# Inputs.net
KiCad netlist of a schematic drawn in Altium Designer
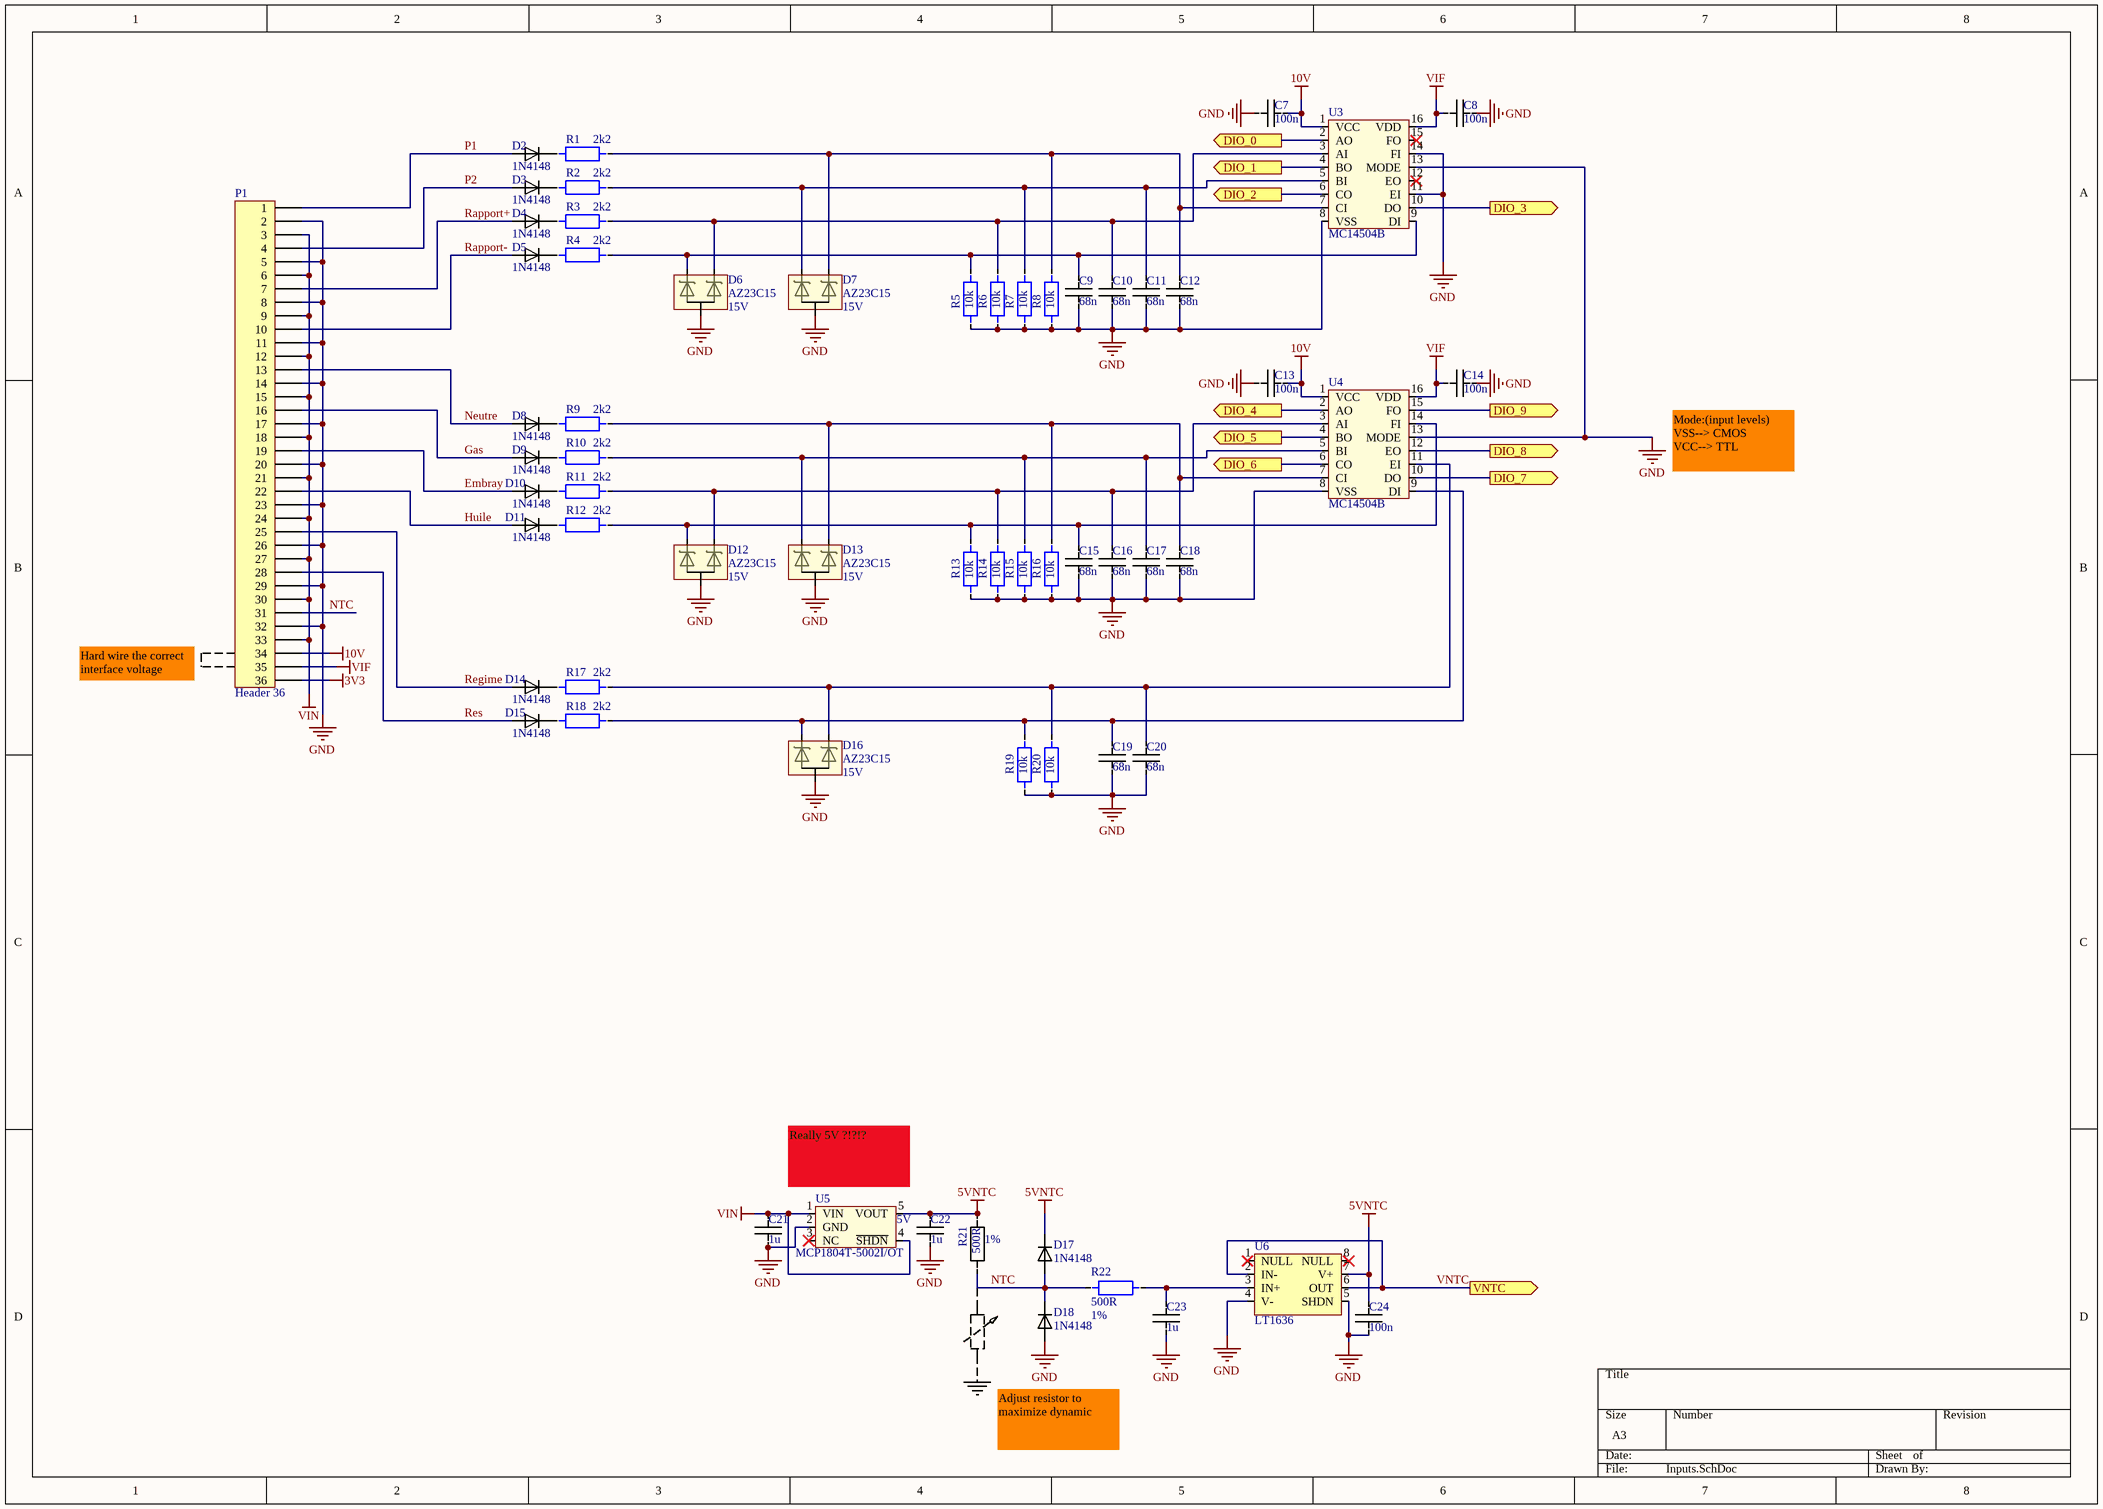
[diagram p0: Inputs.SchDoc]

(export (version "E")
  (design (tool "Eeschema 10.0.6"))
  (components
    (comp (ref "C7")
      (value "100n")
      (footprint "0402_")
      (fields
        (field (name "MANUFACTURER") "TDK Corp.")
        (field (name "MANUFACTURER PARTNUM") "C1005X5R1E104K050BC")
      )
      (libsource (lib "*") (part "C"))
    )
    (comp (ref "C8")
      (value "100n")
      (footprint "0402_")
      (fields
        (field (name "MANUFACTURER") "TDK Corp.")
        (field (name "MANUFACTURER PARTNUM") "C1005X5R1E104K050BC")
      )
      (libsource (lib "*") (part "C"))
    )
    (comp (ref "C9")
      (value "68n")
      (footprint "0603_")
      (fields (field (name "MANUFACTURER") "Samsung") (field (name "MANUFACTURER PARTNUM") "CL10B683KB8NNNC"))
      (libsource (lib "*") (part "C"))
    )
    (comp (ref "C10")
      (value "68n")
      (footprint "0603_")
      (fields (field (name "MANUFACTURER") "Samsung") (field (name "MANUFACTURER PARTNUM") "CL10B683KB8NNNC"))
      (libsource (lib "*") (part "C"))
    )
    (comp (ref "C11")
      (value "68n")
      (footprint "0603_")
      (fields (field (name "MANUFACTURER") "Samsung") (field (name "MANUFACTURER PARTNUM") "CL10B683KB8NNNC"))
      (libsource (lib "*") (part "C"))
    )
    (comp (ref "C12")
      (value "68n")
      (footprint "0603_")
      (fields (field (name "MANUFACTURER") "Samsung") (field (name "MANUFACTURER PARTNUM") "CL10B683KB8NNNC"))
      (libsource (lib "*") (part "C"))
    )
    (comp (ref "C13")
      (value "100n")
      (footprint "0402_")
      (fields
        (field (name "MANUFACTURER") "TDK Corp.")
        (field (name "MANUFACTURER PARTNUM") "C1005X5R1E104K050BC")
      )
      (libsource (lib "*") (part "C"))
    )
    (comp (ref "C14")
      (value "100n")
      (footprint "0402_")
      (fields
        (field (name "MANUFACTURER") "TDK Corp.")
        (field (name "MANUFACTURER PARTNUM") "C1005X5R1E104K050BC")
      )
      (libsource (lib "*") (part "C"))
    )
    (comp (ref "C15")
      (value "68n")
      (footprint "0603_")
      (fields (field (name "MANUFACTURER") "Samsung") (field (name "MANUFACTURER PARTNUM") "CL10B683KB8NNNC"))
      (libsource (lib "*") (part "C"))
    )
    (comp (ref "C16")
      (value "68n")
      (footprint "0603_")
      (fields (field (name "MANUFACTURER") "Samsung") (field (name "MANUFACTURER PARTNUM") "CL10B683KB8NNNC"))
      (libsource (lib "*") (part "C"))
    )
    (comp (ref "C17")
      (value "68n")
      (footprint "0603_")
      (fields (field (name "MANUFACTURER") "Samsung") (field (name "MANUFACTURER PARTNUM") "CL10B683KB8NNNC"))
      (libsource (lib "*") (part "C"))
    )
    (comp (ref "C18")
      (value "68n")
      (footprint "0603_")
      (fields (field (name "MANUFACTURER") "Samsung") (field (name "MANUFACTURER PARTNUM") "CL10B683KB8NNNC"))
      (libsource (lib "*") (part "C"))
    )
    (comp (ref "C19")
      (value "68n")
      (footprint "0603_")
      (fields (field (name "MANUFACTURER") "Samsung") (field (name "MANUFACTURER PARTNUM") "CL10B683KB8NNNC"))
      (libsource (lib "*") (part "C"))
    )
    (comp (ref "C20")
      (value "68n")
      (footprint "0603_")
      (fields (field (name "MANUFACTURER") "Samsung") (field (name "MANUFACTURER PARTNUM") "CL10B683KB8NNNC"))
      (libsource (lib "*") (part "C"))
    )
    (comp (ref "C21")
      (value "1u")
      (footprint "0402_")
      (fields
        (field (name "MANUFACTURER PARTNUM") "GRM155R61E105MA12D")
        (field (name "MANUFACTURER") "Murata")
      )
      (libsource (lib "*") (part "C"))
    )
    (comp (ref "C22")
      (value "1u")
      (footprint "0402_")
      (fields
        (field (name "MANUFACTURER PARTNUM") "GRM155R61E105MA12D")
        (field (name "MANUFACTURER") "Murata")
      )
      (libsource (lib "*") (part "C"))
    )
    (comp (ref "C23")
      (value "1u")
      (footprint "0402_")
      (fields
        (field (name "MANUFACTURER PARTNUM") "GRM155R61E105MA12D")
        (field (name "MANUFACTURER") "Murata")
      )
      (libsource (lib "*") (part "C"))
    )
    (comp (ref "C24")
      (value "100n")
      (footprint "0402_")
      (fields
        (field (name "VOLTAGE") "25V")
        (field (name "MANUFACTURER") "TDK Corp.")
        (field (name "MANUFACTURER PARTNUM") "C1005X5R1E104K050BC")
      )
      (libsource (lib "*") (part "C"))
    )
    (comp (ref "D2")
      (value "1N4148")
      (footprint "SOD323")
      (fields
        (field (name "MANUFACTURER") "Micro Commercial Co")
        (field (name "MANUFACTURER PARTNUM") "1N4148WX-TP")
      )
      (libsource (lib "Sch_GB_lib") (part "1N4148"))
    )
    (comp (ref "D3")
      (value "1N4148")
      (footprint "SOD323")
      (fields
        (field (name "MANUFACTURER") "Micro Commercial Co")
        (field (name "MANUFACTURER PARTNUM") "1N4148WX-TP")
      )
      (libsource (lib "Sch_GB_lib") (part "1N4148"))
    )
    (comp (ref "D4")
      (value "1N4148")
      (footprint "SOD323")
      (fields
        (field (name "MANUFACTURER") "Micro Commercial Co")
        (field (name "MANUFACTURER PARTNUM") "1N4148WX-TP")
      )
      (libsource (lib "Sch_GB_lib") (part "1N4148"))
    )
    (comp (ref "D5")
      (value "1N4148")
      (footprint "SOD323")
      (fields
        (field (name "MANUFACTURER") "Micro Commercial Co")
        (field (name "MANUFACTURER PARTNUM") "1N4148WX-TP")
      )
      (libsource (lib "Sch_GB_lib") (part "1N4148"))
    )
    (comp (ref "D6")
      (value "AZ23C15")
      (footprint "SOT23")
      (description "DIODE ZENER ARRAY 15V SOT23-3")
      (fields
        (field (name "MANUFACTURER PARTNUM") "AZ23C15-7-F")
        (field (name "MANUFACTURER") "Diodes Inc.")
        (field (name "VZ") "15V")
      )
      (libsource (lib "Sch_GB_lib") (part "AZ23C15"))
    )
    (comp (ref "D7")
      (value "AZ23C15")
      (footprint "SOT23")
      (description "DIODE ZENER ARRAY 15V SOT23-3")
      (fields
        (field (name "MANUFACTURER PARTNUM") "AZ23C15-7-F")
        (field (name "MANUFACTURER") "Diodes Inc.")
        (field (name "VZ") "15V")
      )
      (libsource (lib "Sch_GB_lib") (part "AZ23C15"))
    )
    (comp (ref "D8")
      (value "1N4148")
      (footprint "SOD323")
      (fields
        (field (name "MANUFACTURER") "Micro Commercial Co")
        (field (name "MANUFACTURER PARTNUM") "1N4148WX-TP")
      )
      (libsource (lib "Sch_GB_lib") (part "1N4148"))
    )
    (comp (ref "D9")
      (value "1N4148")
      (footprint "SOD323")
      (fields
        (field (name "MANUFACTURER") "Micro Commercial Co")
        (field (name "MANUFACTURER PARTNUM") "1N4148WX-TP")
      )
      (libsource (lib "Sch_GB_lib") (part "1N4148"))
    )
    (comp (ref "D10")
      (value "1N4148")
      (footprint "SOD323")
      (fields
        (field (name "MANUFACTURER") "Micro Commercial Co")
        (field (name "MANUFACTURER PARTNUM") "1N4148WX-TP")
      )
      (libsource (lib "Sch_GB_lib") (part "1N4148"))
    )
    (comp (ref "D11")
      (value "1N4148")
      (footprint "SOD323")
      (fields
        (field (name "MANUFACTURER") "Micro Commercial Co")
        (field (name "MANUFACTURER PARTNUM") "1N4148WX-TP")
      )
      (libsource (lib "Sch_GB_lib") (part "1N4148"))
    )
    (comp (ref "D12")
      (value "AZ23C15")
      (footprint "SOT23")
      (description "DIODE ZENER ARRAY 15V SOT23-3")
      (fields
        (field (name "MANUFACTURER PARTNUM") "AZ23C15-7-F")
        (field (name "MANUFACTURER") "Diodes Inc.")
        (field (name "VZ") "15V")
      )
      (libsource (lib "Sch_GB_lib") (part "AZ23C15"))
    )
    (comp (ref "D13")
      (value "AZ23C15")
      (footprint "SOT23")
      (description "DIODE ZENER ARRAY 15V SOT23-3")
      (fields
        (field (name "MANUFACTURER PARTNUM") "AZ23C15-7-F")
        (field (name "MANUFACTURER") "Diodes Inc.")
        (field (name "VZ") "15V")
      )
      (libsource (lib "Sch_GB_lib") (part "AZ23C15"))
    )
    (comp (ref "D14")
      (value "1N4148")
      (footprint "SOD323")
      (fields
        (field (name "MANUFACTURER") "Micro Commercial Co")
        (field (name "MANUFACTURER PARTNUM") "1N4148WX-TP")
      )
      (libsource (lib "Sch_GB_lib") (part "1N4148"))
    )
    (comp (ref "D15")
      (value "1N4148")
      (footprint "SOD323")
      (fields
        (field (name "MANUFACTURER") "Micro Commercial Co")
        (field (name "MANUFACTURER PARTNUM") "1N4148WX-TP")
      )
      (libsource (lib "Sch_GB_lib") (part "1N4148"))
    )
    (comp (ref "D16")
      (value "AZ23C15")
      (footprint "SOT23")
      (description "DIODE ZENER ARRAY 15V SOT23-3")
      (fields
        (field (name "MANUFACTURER PARTNUM") "AZ23C15-7-F")
        (field (name "MANUFACTURER") "Diodes Inc.")
        (field (name "VZ") "15V")
      )
      (libsource (lib "Sch_GB_lib") (part "AZ23C15"))
    )
    (comp (ref "D17")
      (value "1N4148")
      (footprint "SOD323")
      (fields
        (field (name "MANUFACTURER") "Micro Commercial Co")
        (field (name "MANUFACTURER PARTNUM") "1N4148WX-TP")
      )
      (libsource (lib "Sch_GB_lib") (part "1N4148"))
    )
    (comp (ref "D18")
      (value "1N4148")
      (footprint "SOD323")
      (fields
        (field (name "MANUFACTURER") "Micro Commercial Co")
        (field (name "MANUFACTURER PARTNUM") "1N4148WX-TP")
      )
      (libsource (lib "Sch_GB_lib") (part "1N4148"))
    )
    (comp (ref "P1")
      (value "Header 36")
      (footprint "PHOENIX_PTSA05_36")
      (description "Header, 36-Pin")
      (fields
        (field (name "MANUFACTURER PARTNUM") "1990164")
        (field (name "MANUFACTURER") "Phoenix Contact")
        (field (name "PUBLISHER") "Altium Limited")
      )
      (libsource (lib "Sch_GB_lib") (part "Header 36"))
    )
    (comp (ref "R1")
      (value "2k2")
      (footprint "0805_")
      (fields (field (name "MANUFACTURER") "Yageo") (field (name "MANUFACTURER PARTNUM") "RC0805JR-072K2L"))
      (libsource (lib "*") (part "R"))
    )
    (comp (ref "R2")
      (value "2k2")
      (footprint "0805_")
      (fields (field (name "MANUFACTURER") "Yageo") (field (name "MANUFACTURER PARTNUM") "RC0805JR-072K2L"))
      (libsource (lib "*") (part "R"))
    )
    (comp (ref "R3")
      (value "2k2")
      (footprint "0805_")
      (fields (field (name "MANUFACTURER") "Yageo") (field (name "MANUFACTURER PARTNUM") "RC0805JR-072K2L"))
      (libsource (lib "*") (part "R"))
    )
    (comp (ref "R4")
      (value "2k2")
      (footprint "0805_")
      (fields (field (name "MANUFACTURER") "Yageo") (field (name "MANUFACTURER PARTNUM") "RC0805JR-072K2L"))
      (libsource (lib "*") (part "R"))
    )
    (comp (ref "R5")
      (value "10k")
      (footprint "0402_")
      (fields (field (name "MANUFACTURER PARTNUM") "ERJ-2RKF1002X") (field (name "MANUFACTURER") "Panasonic"))
      (libsource (lib "*") (part "R"))
    )
    (comp (ref "R6")
      (value "10k")
      (footprint "0402_")
      (fields (field (name "MANUFACTURER PARTNUM") "ERJ-2RKF1002X") (field (name "MANUFACTURER") "Panasonic"))
      (libsource (lib "*") (part "R"))
    )
    (comp (ref "R7")
      (value "10k")
      (footprint "0402_")
      (fields (field (name "MANUFACTURER PARTNUM") "ERJ-2RKF1002X") (field (name "MANUFACTURER") "Panasonic"))
      (libsource (lib "*") (part "R"))
    )
    (comp (ref "R8")
      (value "10k")
      (footprint "0402_")
      (fields (field (name "MANUFACTURER PARTNUM") "ERJ-2RKF1002X") (field (name "MANUFACTURER") "Panasonic"))
      (libsource (lib "*") (part "R"))
    )
    (comp (ref "R9")
      (value "2k2")
      (footprint "0805_")
      (fields (field (name "MANUFACTURER") "Yageo") (field (name "MANUFACTURER PARTNUM") "RC0805JR-072K2L"))
      (libsource (lib "*") (part "R"))
    )
    (comp (ref "R10")
      (value "2k2")
      (footprint "0805_")
      (fields (field (name "MANUFACTURER") "Yageo") (field (name "MANUFACTURER PARTNUM") "RC0805JR-072K2L"))
      (libsource (lib "*") (part "R"))
    )
    (comp (ref "R11")
      (value "2k2")
      (footprint "0805_")
      (fields (field (name "MANUFACTURER") "Yageo") (field (name "MANUFACTURER PARTNUM") "RC0805JR-072K2L"))
      (libsource (lib "*") (part "R"))
    )
    (comp (ref "R12")
      (value "2k2")
      (footprint "0805_")
      (fields (field (name "MANUFACTURER") "Yageo") (field (name "MANUFACTURER PARTNUM") "RC0805JR-072K2L"))
      (libsource (lib "*") (part "R"))
    )
    (comp (ref "R13")
      (value "10k")
      (footprint "0402_")
      (fields (field (name "MANUFACTURER PARTNUM") "ERJ-2RKF1002X") (field (name "MANUFACTURER") "Panasonic"))
      (libsource (lib "*") (part "R"))
    )
    (comp (ref "R14")
      (value "10k")
      (footprint "0402_")
      (fields (field (name "MANUFACTURER PARTNUM") "ERJ-2RKF1002X") (field (name "MANUFACTURER") "Panasonic"))
      (libsource (lib "*") (part "R"))
    )
    (comp (ref "R15")
      (value "10k")
      (footprint "0402_")
      (fields (field (name "MANUFACTURER PARTNUM") "ERJ-2RKF1002X") (field (name "MANUFACTURER") "Panasonic"))
      (libsource (lib "*") (part "R"))
    )
    (comp (ref "R16")
      (value "10k")
      (footprint "0402_")
      (fields (field (name "MANUFACTURER PARTNUM") "ERJ-2RKF1002X") (field (name "MANUFACTURER") "Panasonic"))
      (libsource (lib "*") (part "R"))
    )
    (comp (ref "R17")
      (value "2k2")
      (footprint "0805_")
      (fields (field (name "MANUFACTURER") "Yageo") (field (name "MANUFACTURER PARTNUM") "RC0805JR-072K2L"))
      (libsource (lib "*") (part "R"))
    )
    (comp (ref "R18")
      (value "2k2")
      (footprint "0805_")
      (fields (field (name "MANUFACTURER") "Yageo") (field (name "MANUFACTURER PARTNUM") "RC0805JR-072K2L"))
      (libsource (lib "*") (part "R"))
    )
    (comp (ref "R19")
      (value "10k")
      (footprint "0402_")
      (fields (field (name "MANUFACTURER PARTNUM") "ERJ-2RKF1002X") (field (name "MANUFACTURER") "Panasonic"))
      (libsource (lib "*") (part "R"))
    )
    (comp (ref "R20")
      (value "10k")
      (footprint "0402_")
      (fields (field (name "MANUFACTURER PARTNUM") "ERJ-2RKF1002X") (field (name "MANUFACTURER") "Panasonic"))
      (libsource (lib "*") (part "R"))
    )
    (comp (ref "R21")
      (value "500R")
      (footprint "0805_")
      (fields
        (field (name "MANUFACTURER PARTNUM") "RC0805FR-07510RL")
        (field (name "MANUFACTURER") "Yageo")
        (field (name "PRECISION") "1%")
      )
      (libsource (lib "*") (part "R"))
    )
    (comp (ref "R22")
      (value "500R")
      (footprint "0805_")
      (fields
        (field (name "MANUFACTURER PARTNUM") "RC0805FR-07510RL")
        (field (name "MANUFACTURER") "Yageo")
        (field (name "PRECISION") "1%")
      )
      (libsource (lib "*") (part "R"))
    )
    (comp (ref "U3")
      (value "MC14504B")
      (footprint "SOIC16")
      (description "IC LEVEL SHIFTER HEX 16-SOIC")
      (fields (field (name "MANUFACTURER") "On Semi") (field (name "MANUFACTURER PARTNUM") "MC14504BDG"))
      (libsource (lib "Sch_GB_lib") (part "MC14504B"))
    )
    (comp (ref "U4")
      (value "MC14504B")
      (footprint "SOIC16")
      (description "IC LEVEL SHIFTER HEX 16-SOIC")
      (fields (field (name "MANUFACTURER") "On Semi") (field (name "MANUFACTURER PARTNUM") "MC14504BDG"))
      (libsource (lib "Sch_GB_lib") (part "MC14504B"))
    )
    (comp (ref "U5")
      (value "MCP1804T-5002I/OT")
      (footprint "sot23-5")
      (description "IC REG LDO 5V 0.15A SOT23-5")
      (fields (field (name "MANUFACTURER") "Microchip") (field (name "RATED VOLATAGE") "5V"))
      (libsource (lib "Sch_GB_lib") (part "MCP1804T-5002I/OT"))
    )
    (comp (ref "U6")
      (value "LT1636")
      (footprint "soic8")
      (description "IC OPAMP GP 220KHZ RRO 8SO SHTDN")
      (fields
        (field (name "MANUFACTURER PARTNUM") "LT1636CS8#PBF")
        (field (name "MANUFACTURER") "Linear Technology")
      )
      (libsource (lib "Sch_GB_lib") (part "LT1636"))
    )
  )
  (nets
    (net (code "1") (name "/DIO_0") (class "Default")
      (node (ref "U3") (pin "2") (pinfunction "AO_2") (pintype "passive"))
    )
    (net (code "2") (name "/DIO_1") (class "Default")
      (node (ref "U3") (pin "4") (pinfunction "BO_4") (pintype "passive"))
    )
    (net (code "3") (name "/DIO_2") (class "Default")
      (node (ref "U3") (pin "6") (pinfunction "CO_6") (pintype "passive"))
    )
    (net (code "4") (name "/DIO_3") (class "Default")
      (node (ref "U3") (pin "10") (pinfunction "DO_10") (pintype "passive"))
    )
    (net (code "5") (name "/DIO_4") (class "Default")
      (node (ref "U4") (pin "2") (pinfunction "AO_2") (pintype "passive"))
    )
    (net (code "6") (name "/DIO_5") (class "Default")
      (node (ref "U4") (pin "4") (pinfunction "BO_4") (pintype "passive"))
    )
    (net (code "7") (name "/DIO_6") (class "Default")
      (node (ref "U4") (pin "6") (pinfunction "CO_6") (pintype "passive"))
    )
    (net (code "8") (name "/DIO_7") (class "Default")
      (node (ref "U4") (pin "10") (pinfunction "DO_10") (pintype "passive"))
    )
    (net (code "9") (name "/DIO_8") (class "Default")
      (node (ref "U4") (pin "12") (pinfunction "EO_12") (pintype "passive"))
    )
    (net (code "10") (name "/DIO_9") (class "Default")
      (node (ref "U4") (pin "15") (pinfunction "FO_15") (pintype "passive"))
    )
    (net (code "11") (name "/Embray") (class "Default")
      (node (ref "D10") (pin "1") (pinfunction "1_1") (pintype "passive"))
      (node (ref "P1") (pin "19") (pinfunction "19_19") (pintype "passive"))
    )
    (net (code "12") (name "/Gas") (class "Default")
      (node (ref "D9") (pin "1") (pinfunction "1_1") (pintype "passive"))
      (node (ref "P1") (pin "16") (pinfunction "16_16") (pintype "passive"))
    )
    (net (code "13") (name "/Huile") (class "Default")
      (node (ref "D11") (pin "1") (pinfunction "1_1") (pintype "passive"))
      (node (ref "P1") (pin "22") (pinfunction "22_22") (pintype "passive"))
    )
    (net (code "14") (name "/NTC") (class "Default")
      (node (ref "D17") (pin "1") (pinfunction "1_1") (pintype "passive"))
      (node (ref "D18") (pin "2") (pinfunction "2_2") (pintype "passive"))
      (node (ref "P1") (pin "31") (pinfunction "31_31") (pintype "passive"))
      (node (ref "R21") (pin "1") (pinfunction "1_1") (pintype "passive"))
      (node (ref "R22") (pin "2") (pinfunction "2_2") (pintype "passive"))
    )
    (net (code "15") (name "/Neutre") (class "Default")
      (node (ref "D8") (pin "1") (pinfunction "1_1") (pintype "passive"))
      (node (ref "P1") (pin "13") (pinfunction "13_13") (pintype "passive"))
    )
    (net (code "16") (name "/P1") (class "Default")
      (node (ref "D2") (pin "1") (pinfunction "1_1") (pintype "passive"))
      (node (ref "P1") (pin "1") (pinfunction "1_1") (pintype "passive"))
    )
    (net (code "17") (name "/P2") (class "Default")
      (node (ref "D3") (pin "1") (pinfunction "1_1") (pintype "passive"))
      (node (ref "P1") (pin "4") (pinfunction "4_4") (pintype "passive"))
    )
    (net (code "18") (name "/Rapport+") (class "Default")
      (node (ref "D4") (pin "1") (pinfunction "1_1") (pintype "passive"))
      (node (ref "P1") (pin "7") (pinfunction "7_7") (pintype "passive"))
    )
    (net (code "19") (name "/Rapport-") (class "Default")
      (node (ref "D5") (pin "1") (pinfunction "1_1") (pintype "passive"))
      (node (ref "P1") (pin "10") (pinfunction "10_10") (pintype "passive"))
    )
    (net (code "20") (name "/Regime") (class "Default")
      (node (ref "D14") (pin "1") (pinfunction "1_1") (pintype "passive"))
      (node (ref "P1") (pin "25") (pinfunction "25_25") (pintype "passive"))
    )
    (net (code "21") (name "/Res") (class "Default")
      (node (ref "D15") (pin "1") (pinfunction "1_1") (pintype "passive"))
      (node (ref "P1") (pin "28") (pinfunction "28_28") (pintype "passive"))
    )
    (net (code "22") (name "/VNTC") (class "Default")
      (node (ref "U6") (pin "2") (pinfunction "IN-_2") (pintype "passive"))
      (node (ref "U6") (pin "6") (pinfunction "OUT_6") (pintype "passive"))
    )
    (net (code "23") (name "3V3") (class "Default")
      (node (ref "P1") (pin "36") (pinfunction "36_36") (pintype "passive"))
    )
    (net (code "24") (name "5VNTC") (class "Default")
      (node (ref "C22") (pin "1") (pinfunction "1_1") (pintype "passive"))
      (node (ref "C24") (pin "1") (pinfunction "1_1") (pintype "passive"))
      (node (ref "D17") (pin "2") (pinfunction "2_2") (pintype "passive"))
      (node (ref "R21") (pin "2") (pinfunction "2_2") (pintype "passive"))
      (node (ref "U5") (pin "5") (pinfunction "VOUT_5") (pintype "passive"))
      (node (ref "U6") (pin "7") (pinfunction "V+_7") (pintype "passive"))
    )
    (net (code "25") (name "10V") (class "Default")
      (node (ref "C13") (pin "1") (pinfunction "1_1") (pintype "passive"))
      (node (ref "C7") (pin "1") (pinfunction "1_1") (pintype "passive"))
      (node (ref "P1") (pin "34") (pinfunction "34_34") (pintype "passive"))
      (node (ref "U3") (pin "1") (pinfunction "VCC_1") (pintype "passive"))
      (node (ref "U4") (pin "1") (pinfunction "VCC_1") (pintype "passive"))
    )
    (net (code "26") (name "GND") (class "Default")
      (node (ref "C10") (pin "1") (pinfunction "1_1") (pintype "passive"))
      (node (ref "C11") (pin "1") (pinfunction "1_1") (pintype "passive"))
      (node (ref "C12") (pin "1") (pinfunction "1_1") (pintype "passive"))
      (node (ref "C13") (pin "2") (pinfunction "2_2") (pintype "passive"))
      (node (ref "C14") (pin "1") (pinfunction "1_1") (pintype "passive"))
      (node (ref "C15") (pin "1") (pinfunction "1_1") (pintype "passive"))
      (node (ref "C16") (pin "1") (pinfunction "1_1") (pintype "passive"))
      (node (ref "C17") (pin "1") (pinfunction "1_1") (pintype "passive"))
      (node (ref "C18") (pin "1") (pinfunction "1_1") (pintype "passive"))
      (node (ref "C19") (pin "1") (pinfunction "1_1") (pintype "passive"))
      (node (ref "C20") (pin "1") (pinfunction "1_1") (pintype "passive"))
      (node (ref "C21") (pin "2") (pinfunction "2_2") (pintype "passive"))
      (node (ref "C22") (pin "2") (pinfunction "2_2") (pintype "passive"))
      (node (ref "C23") (pin "2") (pinfunction "2_2") (pintype "passive"))
      (node (ref "C24") (pin "2") (pinfunction "2_2") (pintype "passive"))
      (node (ref "C7") (pin "2") (pinfunction "2_2") (pintype "passive"))
      (node (ref "C8") (pin "1") (pinfunction "1_1") (pintype "passive"))
      (node (ref "C9") (pin "1") (pinfunction "1_1") (pintype "passive"))
      (node (ref "D12") (pin "3") (pinfunction "3_3") (pintype "passive"))
      (node (ref "D13") (pin "3") (pinfunction "3_3") (pintype "passive"))
      (node (ref "D16") (pin "3") (pinfunction "3_3") (pintype "passive"))
      (node (ref "D18") (pin "1") (pinfunction "1_1") (pintype "passive"))
      (node (ref "D6") (pin "3") (pinfunction "3_3") (pintype "passive"))
      (node (ref "D7") (pin "3") (pinfunction "3_3") (pintype "passive"))
      (node (ref "P1") (pin "11") (pinfunction "11_11") (pintype "passive"))
      (node (ref "P1") (pin "14") (pinfunction "14_14") (pintype "passive"))
      (node (ref "P1") (pin "17") (pinfunction "17_17") (pintype "passive"))
      (node (ref "P1") (pin "2") (pinfunction "2_2") (pintype "passive"))
      (node (ref "P1") (pin "20") (pinfunction "20_20") (pintype "passive"))
      (node (ref "P1") (pin "23") (pinfunction "23_23") (pintype "passive"))
      (node (ref "P1") (pin "26") (pinfunction "26_26") (pintype "passive"))
      (node (ref "P1") (pin "29") (pinfunction "29_29") (pintype "passive"))
      (node (ref "P1") (pin "32") (pinfunction "32_32") (pintype "passive"))
      (node (ref "P1") (pin "5") (pinfunction "5_5") (pintype "passive"))
      (node (ref "P1") (pin "8") (pinfunction "8_8") (pintype "passive"))
      (node (ref "R13") (pin "1") (pinfunction "1_1") (pintype "passive"))
      (node (ref "R14") (pin "1") (pinfunction "1_1") (pintype "passive"))
      (node (ref "R15") (pin "1") (pinfunction "1_1") (pintype "passive"))
      (node (ref "R16") (pin "1") (pinfunction "1_1") (pintype "passive"))
      (node (ref "R19") (pin "1") (pinfunction "1_1") (pintype "passive"))
      (node (ref "R20") (pin "1") (pinfunction "1_1") (pintype "passive"))
      (node (ref "R5") (pin "1") (pinfunction "1_1") (pintype "passive"))
      (node (ref "R6") (pin "1") (pinfunction "1_1") (pintype "passive"))
      (node (ref "R7") (pin "1") (pinfunction "1_1") (pintype "passive"))
      (node (ref "R8") (pin "1") (pinfunction "1_1") (pintype "passive"))
      (node (ref "U3") (pin "11") (pinfunction "EI_11") (pintype "passive"))
      (node (ref "U3") (pin "13") (pinfunction "MODE_13") (pintype "passive"))
      (node (ref "U3") (pin "14") (pinfunction "FI_14") (pintype "passive"))
      (node (ref "U3") (pin "8") (pinfunction "VSS_8") (pintype "passive"))
      (node (ref "U4") (pin "13") (pinfunction "MODE_13") (pintype "passive"))
      (node (ref "U4") (pin "8") (pinfunction "VSS_8") (pintype "passive"))
      (node (ref "U5") (pin "2") (pinfunction "GND_2") (pintype "passive"))
      (node (ref "U6") (pin "4") (pinfunction "V-_4") (pintype "passive"))
      (node (ref "U6") (pin "5") (pinfunction "SHDN_5") (pintype "passive"))
    )
    (net (code "27") (name "Net-(D2-Pad2)") (class "Default")
      (node (ref "D2") (pin "2") (pinfunction "2_2") (pintype "passive"))
      (node (ref "R1") (pin "2") (pinfunction "2_2") (pintype "passive"))
    )
    (net (code "28") (name "Net-(D3-Pad2)") (class "Default")
      (node (ref "D3") (pin "2") (pinfunction "2_2") (pintype "passive"))
      (node (ref "R2") (pin "2") (pinfunction "2_2") (pintype "passive"))
    )
    (net (code "29") (name "Net-(D4-Pad2)") (class "Default")
      (node (ref "D4") (pin "2") (pinfunction "2_2") (pintype "passive"))
      (node (ref "R3") (pin "2") (pinfunction "2_2") (pintype "passive"))
    )
    (net (code "30") (name "Net-(D5-Pad2)") (class "Default")
      (node (ref "D5") (pin "2") (pinfunction "2_2") (pintype "passive"))
      (node (ref "R4") (pin "2") (pinfunction "2_2") (pintype "passive"))
    )
    (net (code "31") (name "Net-(D8-Pad2)") (class "Default")
      (node (ref "D8") (pin "2") (pinfunction "2_2") (pintype "passive"))
      (node (ref "R9") (pin "2") (pinfunction "2_2") (pintype "passive"))
    )
    (net (code "32") (name "Net-(D9-Pad2)") (class "Default")
      (node (ref "D9") (pin "2") (pinfunction "2_2") (pintype "passive"))
      (node (ref "R10") (pin "2") (pinfunction "2_2") (pintype "passive"))
    )
    (net (code "33") (name "Net-(D10-Pad2)") (class "Default")
      (node (ref "D10") (pin "2") (pinfunction "2_2") (pintype "passive"))
      (node (ref "R11") (pin "2") (pinfunction "2_2") (pintype "passive"))
    )
    (net (code "34") (name "Net-(D11-Pad2)") (class "Default")
      (node (ref "D11") (pin "2") (pinfunction "2_2") (pintype "passive"))
      (node (ref "R12") (pin "2") (pinfunction "2_2") (pintype "passive"))
    )
    (net (code "35") (name "Net-(D14-Pad2)") (class "Default")
      (node (ref "D14") (pin "2") (pinfunction "2_2") (pintype "passive"))
      (node (ref "R17") (pin "2") (pinfunction "2_2") (pintype "passive"))
    )
    (net (code "36") (name "Net-(D15-Pad2)") (class "Default")
      (node (ref "D15") (pin "2") (pinfunction "2_2") (pintype "passive"))
      (node (ref "R18") (pin "2") (pinfunction "2_2") (pintype "passive"))
    )
    (net (code "37") (name "Net-(U3-AI)") (class "Default")
      (node (ref "C10") (pin "2") (pinfunction "2_2") (pintype "passive"))
      (node (ref "D6") (pin "1") (pinfunction "1_1") (pintype "passive"))
      (node (ref "R3") (pin "1") (pinfunction "1_1") (pintype "passive"))
      (node (ref "R6") (pin "2") (pinfunction "2_2") (pintype "passive"))
      (node (ref "U3") (pin "3") (pinfunction "AI_3") (pintype "passive"))
    )
    (net (code "38") (name "Net-(U3-BI)") (class "Default")
      (node (ref "C11") (pin "2") (pinfunction "2_2") (pintype "passive"))
      (node (ref "D7") (pin "2") (pinfunction "2_2") (pintype "passive"))
      (node (ref "R2") (pin "1") (pinfunction "1_1") (pintype "passive"))
      (node (ref "R7") (pin "2") (pinfunction "2_2") (pintype "passive"))
      (node (ref "U3") (pin "5") (pinfunction "BI_5") (pintype "passive"))
    )
    (net (code "39") (name "Net-(U3-CI)") (class "Default")
      (node (ref "C12") (pin "2") (pinfunction "2_2") (pintype "passive"))
      (node (ref "D7") (pin "1") (pinfunction "1_1") (pintype "passive"))
      (node (ref "R1") (pin "1") (pinfunction "1_1") (pintype "passive"))
      (node (ref "R8") (pin "2") (pinfunction "2_2") (pintype "passive"))
      (node (ref "U3") (pin "7") (pinfunction "CI_7") (pintype "passive"))
    )
    (net (code "40") (name "Net-(U3-DI)") (class "Default")
      (node (ref "C9") (pin "2") (pinfunction "2_2") (pintype "passive"))
      (node (ref "D6") (pin "2") (pinfunction "2_2") (pintype "passive"))
      (node (ref "R4") (pin "1") (pinfunction "1_1") (pintype "passive"))
      (node (ref "R5") (pin "2") (pinfunction "2_2") (pintype "passive"))
      (node (ref "U3") (pin "9") (pinfunction "DI_9") (pintype "passive"))
    )
    (net (code "41") (name "Net-(U4-AI)") (class "Default")
      (node (ref "C16") (pin "2") (pinfunction "2_2") (pintype "passive"))
      (node (ref "D12") (pin "1") (pinfunction "1_1") (pintype "passive"))
      (node (ref "R11") (pin "1") (pinfunction "1_1") (pintype "passive"))
      (node (ref "R14") (pin "2") (pinfunction "2_2") (pintype "passive"))
      (node (ref "U4") (pin "3") (pinfunction "AI_3") (pintype "passive"))
    )
    (net (code "42") (name "Net-(U4-BI)") (class "Default")
      (node (ref "C17") (pin "2") (pinfunction "2_2") (pintype "passive"))
      (node (ref "D13") (pin "2") (pinfunction "2_2") (pintype "passive"))
      (node (ref "R10") (pin "1") (pinfunction "1_1") (pintype "passive"))
      (node (ref "R15") (pin "2") (pinfunction "2_2") (pintype "passive"))
      (node (ref "U4") (pin "5") (pinfunction "BI_5") (pintype "passive"))
    )
    (net (code "43") (name "Net-(U4-CI)") (class "Default")
      (node (ref "C18") (pin "2") (pinfunction "2_2") (pintype "passive"))
      (node (ref "D13") (pin "1") (pinfunction "1_1") (pintype "passive"))
      (node (ref "R16") (pin "2") (pinfunction "2_2") (pintype "passive"))
      (node (ref "R9") (pin "1") (pinfunction "1_1") (pintype "passive"))
      (node (ref "U4") (pin "7") (pinfunction "CI_7") (pintype "passive"))
    )
    (net (code "44") (name "Net-(U4-DI)") (class "Default")
      (node (ref "C19") (pin "2") (pinfunction "2_2") (pintype "passive"))
      (node (ref "D16") (pin "2") (pinfunction "2_2") (pintype "passive"))
      (node (ref "R18") (pin "1") (pinfunction "1_1") (pintype "passive"))
      (node (ref "R19") (pin "2") (pinfunction "2_2") (pintype "passive"))
      (node (ref "U4") (pin "9") (pinfunction "DI_9") (pintype "passive"))
    )
    (net (code "45") (name "Net-(U4-EI)") (class "Default")
      (node (ref "C20") (pin "2") (pinfunction "2_2") (pintype "passive"))
      (node (ref "D16") (pin "1") (pinfunction "1_1") (pintype "passive"))
      (node (ref "R17") (pin "1") (pinfunction "1_1") (pintype "passive"))
      (node (ref "R20") (pin "2") (pinfunction "2_2") (pintype "passive"))
      (node (ref "U4") (pin "11") (pinfunction "EI_11") (pintype "passive"))
    )
    (net (code "46") (name "Net-(U4-FI)") (class "Default")
      (node (ref "C15") (pin "2") (pinfunction "2_2") (pintype "passive"))
      (node (ref "D12") (pin "2") (pinfunction "2_2") (pintype "passive"))
      (node (ref "R12") (pin "1") (pinfunction "1_1") (pintype "passive"))
      (node (ref "R13") (pin "2") (pinfunction "2_2") (pintype "passive"))
      (node (ref "U4") (pin "14") (pinfunction "FI_14") (pintype "passive"))
    )
    (net (code "47") (name "Net-(U6-IN+)") (class "Default")
      (node (ref "C23") (pin "1") (pinfunction "1_1") (pintype "passive"))
      (node (ref "R22") (pin "1") (pinfunction "1_1") (pintype "passive"))
      (node (ref "U6") (pin "3") (pinfunction "IN+_3") (pintype "passive"))
    )
    (net (code "48") (name "VIF") (class "Default")
      (node (ref "C14") (pin "2") (pinfunction "2_2") (pintype "passive"))
      (node (ref "C8") (pin "2") (pinfunction "2_2") (pintype "passive"))
      (node (ref "P1") (pin "35") (pinfunction "35_35") (pintype "passive"))
      (node (ref "U3") (pin "16") (pinfunction "VDD_16") (pintype "passive"))
      (node (ref "U4") (pin "16") (pinfunction "VDD_16") (pintype "passive"))
    )
    (net (code "49") (name "VIN") (class "Default")
      (node (ref "C21") (pin "1") (pinfunction "1_1") (pintype "passive"))
      (node (ref "P1") (pin "12") (pinfunction "12_12") (pintype "passive"))
      (node (ref "P1") (pin "15") (pinfunction "15_15") (pintype "passive"))
      (node (ref "P1") (pin "18") (pinfunction "18_18") (pintype "passive"))
      (node (ref "P1") (pin "21") (pinfunction "21_21") (pintype "passive"))
      (node (ref "P1") (pin "24") (pinfunction "24_24") (pintype "passive"))
      (node (ref "P1") (pin "27") (pinfunction "27_27") (pintype "passive"))
      (node (ref "P1") (pin "3") (pinfunction "3_3") (pintype "passive"))
      (node (ref "P1") (pin "30") (pinfunction "30_30") (pintype "passive"))
      (node (ref "P1") (pin "33") (pinfunction "33_33") (pintype "passive"))
      (node (ref "P1") (pin "6") (pinfunction "6_6") (pintype "passive"))
      (node (ref "P1") (pin "9") (pinfunction "9_9") (pintype "passive"))
      (node (ref "U5") (pin "1") (pinfunction "VIN_1") (pintype "passive"))
      (node (ref "U5") (pin "4") (pinfunction "~{SHDN}_4") (pintype "passive"))
    )
    (net (code "50") (name "unconnected-(U3-EO-Pad12)") (class "Default")
      (node (ref "U3") (pin "12") (pinfunction "EO_12") (pintype "passive+no_connect"))
    )
    (net (code "51") (name "unconnected-(U3-FO-Pad15)") (class "Default")
      (node (ref "U3") (pin "15") (pinfunction "FO_15") (pintype "passive+no_connect"))
    )
    (net (code "52") (name "unconnected-(U5-NC-Pad3)") (class "Default")
      (node (ref "U5") (pin "3") (pinfunction "NC_3") (pintype "passive+no_connect"))
    )
    (net (code "53") (name "unconnected-(U6-NULL-Pad1)") (class "Default")
      (node (ref "U6") (pin "1") (pinfunction "NULL_1") (pintype "passive+no_connect"))
    )
    (net (code "54") (name "unconnected-(U6-NULL-Pad8)") (class "Default")
      (node (ref "U6") (pin "8") (pinfunction "NULL_8") (pintype "passive+no_connect"))
    )
  )
)
